# POWER.net
KiCad netlist of a schematic drawn in Altium Designer
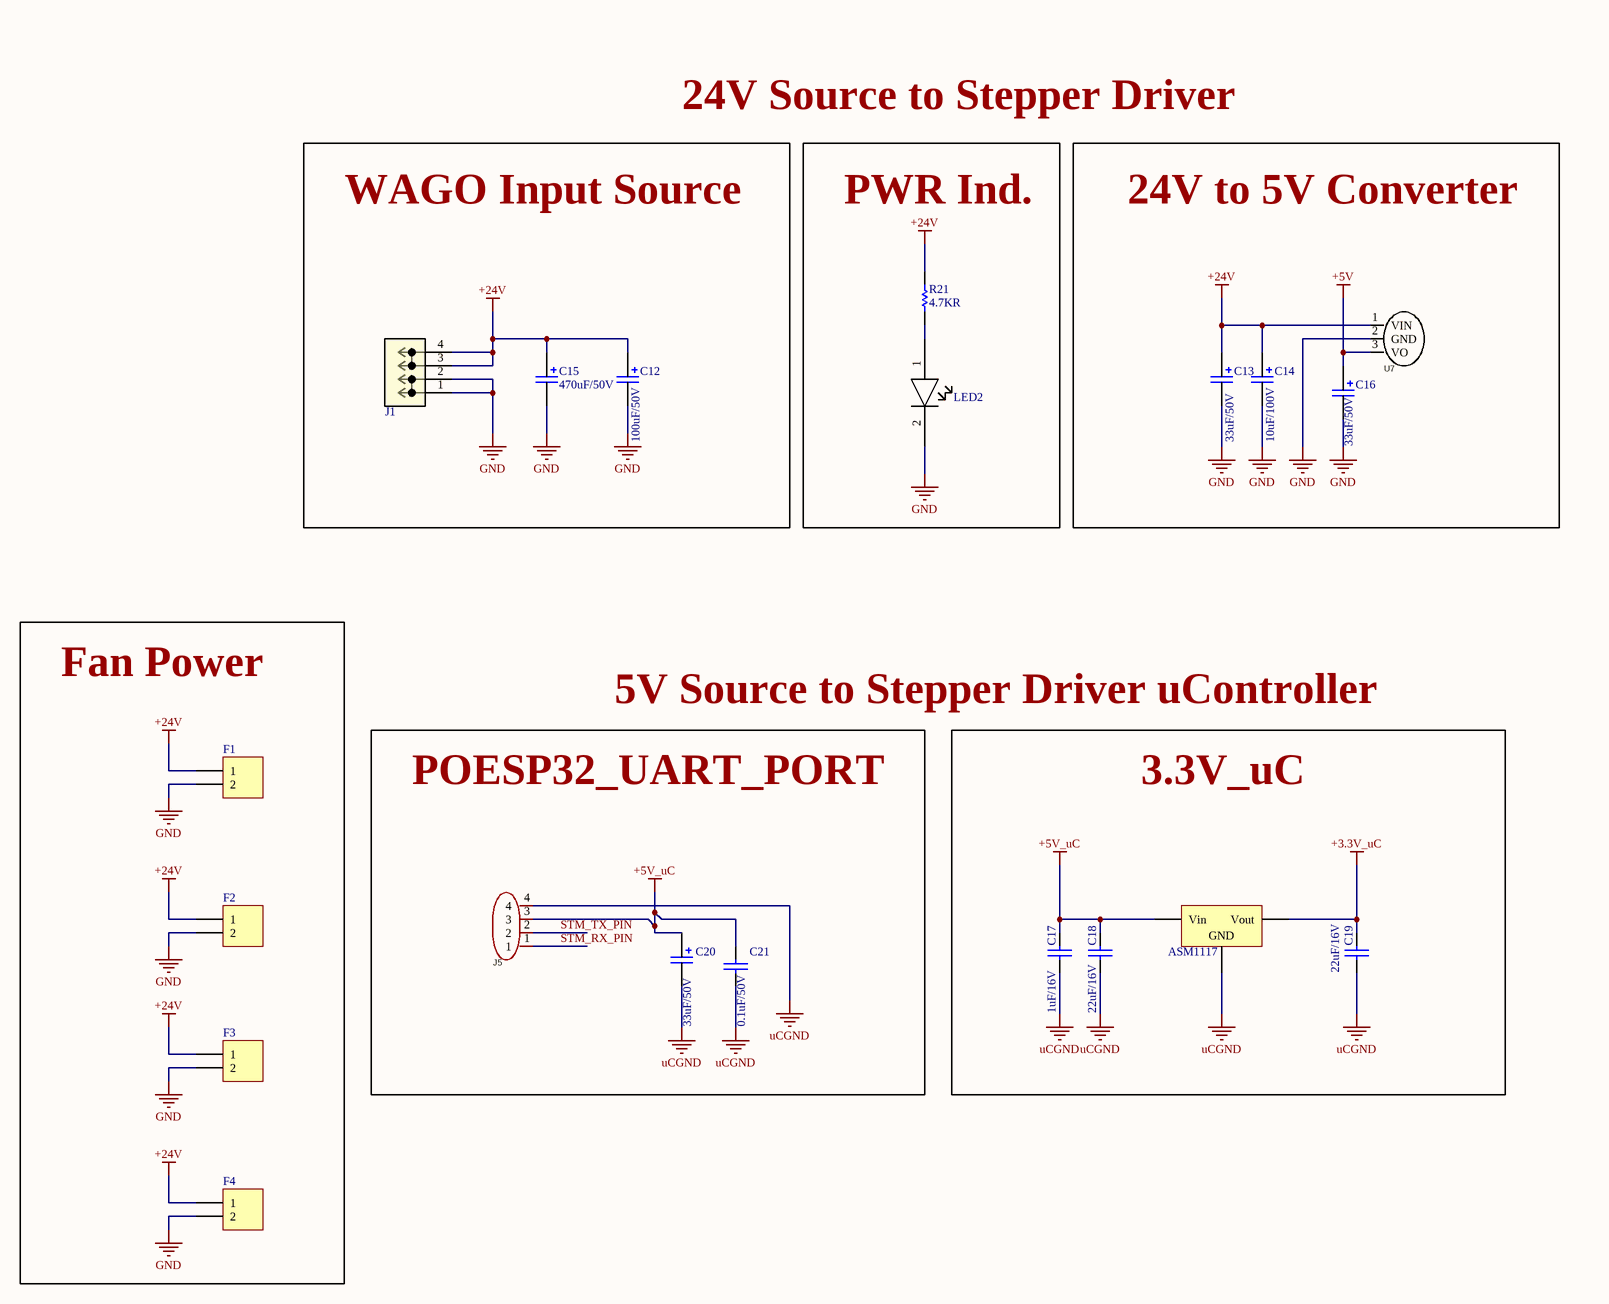
[diagram p0: POWER.SchDoc]

(export (version "E")
  (design (tool "Eeschema 10.0.6"))
  (components
    (comp (ref "ASM1117")
      (value "AMS1117 - 3.3V Reg")
      (footprint "SOT229P700X180-4N")
      (description "C347222")
      (fields (field (name "CREATED BY") "NourAldin"))
      (libsource (lib "AMS1117 - 3.3V Reg") (part "AMS1117 - 3.3V Reg"))
    )
    (comp (ref "C12")
      (value "100uF/50V")
      (footprint "CAPLEAD_D6.3mm")
      (description "C47891")
      (fields
        (field (name "MANUFACTURER") "KEMET")
        (field (name "MANUFACTURER PART NUMBER") "A759EQ475M2AAAE160")
      )
      (libsource (lib "GlobalLib") (part "A759EQ475M2AAAE160"))
    )
    (comp (ref "C13")
      (value "33uF/50V")
      (footprint "CAPLEAD_D6.3mm")
      (description "C45099")
      (fields
        (field (name "MANUFACTURER") "KEMET")
        (field (name "MANUFACTURER PART NUMBER") "A759EQ475M2AAAE160")
      )
      (libsource (lib "GlobalLib") (part "A759EQ475M2AAAE160"))
    )
    (comp (ref "C14")
      (value "10uF/100V")
      (footprint "CAPLEAD_D6.3mm")
      (description "C2029")
      (fields
        (field (name "MANUFACTURER") "KEMET")
        (field (name "MANUFACTURER PART NUMBER") "A759EQ475M2AAAE160")
      )
      (libsource (lib "GlobalLib") (part "A759EQ475M2AAAE160"))
    )
    (comp (ref "C15")
      (value "470uF/50V")
      (footprint "CAPLEAD_D10mm")
      (description "C2960279")
      (fields
        (field (name "MANUFACTURER") "Vishay BCcomponents")
        (field (name "MANUFACTURER PART NUMBER") "MAL215058101E3")
      )
      (libsource (lib "GlobalLib") (part "MAL215058101E3"))
    )
    (comp (ref "C16")
      (value "33uF/50V")
      (footprint "CAPLEAD_D6.3mm")
      (description "C45099")
      (fields
        (field (name "MANUFACTURER") "KEMET")
        (field (name "MANUFACTURER PART NUMBER") "A759EQ475M2AAAE160")
      )
      (libsource (lib "GlobalLib") (part "A759EQ475M2AAAE160"))
    )
    (comp (ref "C17")
      (value "1uF/16V")
      (footprint "PCBComponent_1")
      (description "C1592")
      (fields (field (name "CREATED BY") "NourAldin"))
      (libsource (lib "0603 Capacitor") (part "0603 Capacitor"))
    )
    (comp (ref "C18")
      (value "22uF/16V")
      (footprint "PCBComponent_1")
      (description "C2762594")
      (fields (field (name "CREATED BY") "NourAldin"))
      (libsource (lib "0603 Capacitor") (part "0603 Capacitor"))
    )
    (comp (ref "C19")
      (value "22uF/16V")
      (footprint "PCBComponent_1")
      (description "C2762594")
      (fields (field (name "CREATED BY") "NourAldin"))
      (libsource (lib "0603 Capacitor") (part "0603 Capacitor"))
    )
    (comp (ref "C20")
      (value "33uF/50V")
      (footprint "CAPLEAD_D6.3mm")
      (description "C45099")
      (fields
        (field (name "MANUFACTURER") "KEMET")
        (field (name "MANUFACTURER PART NUMBER") "A759EQ475M2AAAE160")
      )
      (libsource (lib "GlobalLib") (part "A759EQ475M2AAAE160"))
    )
    (comp (ref "C21")
      (value "0.1uF/50V")
      (footprint "PCBComponent_1")
      (description "C1591")
      (fields (field (name "CREATED BY") "NourAldin"))
      (libsource (lib "0603 Capacitor") (part "0603 Capacitor"))
    )
    (comp (ref "F1")
      (value "~")
      (footprint "PinHeader Polar")
      (description "Header 2 pin")
      (fields (field (name "CREATED BY") "NourAldin"))
      (libsource (lib "Header 2 pin") (part "Header 2 pin"))
    )
    (comp (ref "F2")
      (value "~")
      (footprint "PinHeader Polar")
      (description "Header 2 pin")
      (fields (field (name "CREATED BY") "NourAldin"))
      (libsource (lib "Header 2 pin") (part "Header 2 pin"))
    )
    (comp (ref "F3")
      (value "~")
      (footprint "PinHeader Polar")
      (description "Header 2 pin")
      (fields (field (name "CREATED BY") "NourAldin"))
      (libsource (lib "Header 2 pin") (part "Header 2 pin"))
    )
    (comp (ref "F4")
      (value "~")
      (footprint "PinHeader Polar")
      (description "Header 2 pin")
      (fields (field (name "CREATED BY") "NourAldin"))
      (libsource (lib "Header 2 pin") (part "Header 2 pin"))
    )
    (comp (ref "J1")
      (value "Terminal Block")
      (footprint "CONN2_235-402331-000_WAGO")
      (description "C7461083")
      (libsource (lib "LIB") (part "235-402331-000"))
    )
    (comp (ref "J5")
      (value "Header 4P*2mm")
      (footprint "CONN-TH_4P-P2.00_HX20020-4A_2")
      (description "C42372479")
      (fields (field (name "MANUFACTURER") "Megastar(兆星)") (field (name "MANUFACTURER PART") "ZX-HY2.0-4PZZ"))
      (libsource (lib "LIB") (part "ZX-HY2.0-4PZZ"))
    )
    (comp (ref "LED2")
      (value "1206 LED")
      (footprint "1206 LED")
      (description "C434442")
      (fields (field (name "CREATED BY") "NourAldin"))
      (libsource (lib "1206 LED") (part "1206 LED"))
    )
    (comp (ref "R21")
      (value "4.7KR")
      (footprint "R0402")
      (description "C105871")
      (libsource (lib "DIVERSE") (part "0402 Resistor"))
    )
    (comp (ref "U7")
      (value "C5369649")
      (footprint "SIP-3")
      (fields (field (name "MANUFACTURER") "YLPTEC(易川)") (field (name "MANUFACTURER PART") "K7805M-1000R3"))
      (libsource (lib "LIB") (part "K7805M-1000R3_C5369649"))
    )
  )
  (nets
    (net (code "1") (name "+3.3V_uC") (class "Default")
      (node (ref "ASM1117") (pin "Vout") (pinfunction "Vout_Vout") (pintype "passive"))
      (node (ref "C19") (pin "2") (pinfunction "2_2") (pintype "passive"))
    )
    (net (code "2") (name "+5V") (class "Default")
      (node (ref "C16") (pin "1") (pinfunction "1_1") (pintype "passive"))
      (node (ref "U7") (pin "3") (pinfunction "VO_3") (pintype "passive"))
    )
    (net (code "3") (name "+5V_uC") (class "Default")
      (node (ref "ASM1117") (pin "Vin") (pinfunction "Vin_Vin") (pintype "passive"))
      (node (ref "C17") (pin "2") (pinfunction "2_2") (pintype "passive"))
      (node (ref "C18") (pin "2") (pinfunction "2_2") (pintype "passive"))
      (node (ref "C20") (pin "1") (pinfunction "1_1") (pintype "passive"))
      (node (ref "C21") (pin "2") (pinfunction "2_2") (pintype "passive"))
      (node (ref "J5") (pin "3") (pinfunction "3_3") (pintype "passive"))
    )
    (net (code "4") (name "+24V") (class "Default")
      (node (ref "C12") (pin "1") (pinfunction "1_1") (pintype "passive"))
      (node (ref "C13") (pin "1") (pinfunction "1_1") (pintype "passive"))
      (node (ref "C14") (pin "1") (pinfunction "1_1") (pintype "passive"))
      (node (ref "C15") (pin "1") (pinfunction "1_1") (pintype "passive"))
      (node (ref "F1") (pin "1") (pinfunction "1_1") (pintype "passive"))
      (node (ref "F2") (pin "1") (pinfunction "1_1") (pintype "passive"))
      (node (ref "F3") (pin "1") (pinfunction "1_1") (pintype "passive"))
      (node (ref "F4") (pin "1") (pinfunction "1_1") (pintype "passive"))
      (node (ref "J1") (pin "3") (pinfunction "2_1_3") (pintype "passive"))
      (node (ref "J1") (pin "4") (pinfunction "2_2_4") (pintype "passive"))
      (node (ref "R21") (pin "1") (pinfunction "1_1") (pintype "passive"))
      (node (ref "U7") (pin "1") (pinfunction "VIN_1") (pintype "passive"))
    )
    (net (code "5") (name "/STM_RX_PIN") (class "Default")
      (node (ref "J5") (pin "1") (pinfunction "1_1") (pintype "passive"))
    )
    (net (code "6") (name "/STM_TX_PIN") (class "Default")
      (node (ref "J5") (pin "2") (pinfunction "2_2") (pintype "passive"))
    )
    (net (code "7") (name "GND") (class "Default")
      (node (ref "C12") (pin "2") (pinfunction "2_2") (pintype "passive"))
      (node (ref "C13") (pin "2") (pinfunction "2_2") (pintype "passive"))
      (node (ref "C14") (pin "2") (pinfunction "2_2") (pintype "passive"))
      (node (ref "C15") (pin "2") (pinfunction "2_2") (pintype "passive"))
      (node (ref "C16") (pin "2") (pinfunction "2_2") (pintype "passive"))
      (node (ref "F1") (pin "2") (pinfunction "2_2") (pintype "passive"))
      (node (ref "F2") (pin "2") (pinfunction "2_2") (pintype "passive"))
      (node (ref "F3") (pin "2") (pinfunction "2_2") (pintype "passive"))
      (node (ref "F4") (pin "2") (pinfunction "2_2") (pintype "passive"))
      (node (ref "J1") (pin "1") (pinfunction "1_1_1") (pintype "passive"))
      (node (ref "J1") (pin "2") (pinfunction "1_2_2") (pintype "passive"))
      (node (ref "LED2") (pin "2") (pinfunction "2_2") (pintype "passive"))
      (node (ref "U7") (pin "2") (pinfunction "GND_2") (pintype "passive"))
    )
    (net (code "8") (name "Net-(LED2-Pad1)") (class "Default")
      (node (ref "LED2") (pin "1") (pinfunction "1_1") (pintype "passive"))
      (node (ref "R21") (pin "2") (pinfunction "2_2") (pintype "passive"))
    )
    (net (code "9") (name "uCGND") (class "Default")
      (node (ref "ASM1117") (pin "GND") (pinfunction "GND_GND") (pintype "passive"))
      (node (ref "C17") (pin "1") (pinfunction "1_1") (pintype "passive"))
      (node (ref "C18") (pin "1") (pinfunction "1_1") (pintype "passive"))
      (node (ref "C19") (pin "1") (pinfunction "1_1") (pintype "passive"))
      (node (ref "C20") (pin "2") (pinfunction "2_2") (pintype "passive"))
      (node (ref "C21") (pin "1") (pinfunction "1_1") (pintype "passive"))
      (node (ref "J5") (pin "4") (pinfunction "4_4") (pintype "passive"))
    )
  )
)
